# AD620_AC.net
KiCad netlist of a schematic drawn in EAGLE
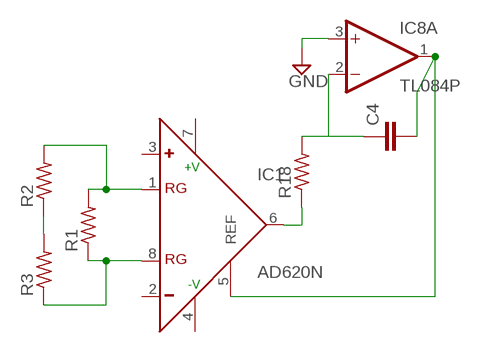
[diagram p0: schematic, sheet 1]

(export (version "E")
  (design (tool "Eeschema 10.0.6"))
  (components
    (comp (ref "C4")
      (value "C-EU050-030X075")
      (footprint "eagle-import:C050-030X075")
      (libsource (lib "eagle-import") (part "C-EU050-030X075"))
    )
    (comp (ref "IC1")
      (value "AD620N")
      (footprint "eagle-import:DIL08")
      (fields (field (name "MF") "ALTERA CORPORATION") (field (name "MPN") "AD620AN"))
      (libsource (lib "eagle-import") (part "AD620N"))
    )
    (comp (ref "IC8")
      (value "TL084P")
      (footprint "eagle-import:DIL14")
      (libsource (lib "eagle-import") (part "TL084P"))
    )
    (comp (ref "R1")
      (value "R-US_0204/5")
      (footprint "eagle-import:0204_5")
      (libsource (lib "eagle-import") (part "R-US_0204/5"))
    )
    (comp (ref "R2")
      (value "R-US_0204/5")
      (footprint "eagle-import:0204_5")
      (libsource (lib "eagle-import") (part "R-US_0204/5"))
    )
    (comp (ref "R3")
      (value "R-US_0204/5")
      (footprint "eagle-import:0204_5")
      (libsource (lib "eagle-import") (part "R-US_0204/5"))
    )
    (comp (ref "R18")
      (value "R-US_0204/5")
      (footprint "eagle-import:0204_5")
      (libsource (lib "eagle-import") (part "R-US_0204/5"))
    )
  )
  (nets
    (net (code "1") (name "/+V") (class "Default")
      (node (ref "IC1") (pin "7") (pinfunction "+V_7") (pintype "power_in"))
    )
    (net (code "2") (name "/-V") (class "Default")
      (node (ref "IC1") (pin "4") (pinfunction "-V_4") (pintype "power_in"))
    )
    (net (code "3") (name "GND") (class "Default")
      (node (ref "IC8") (pin "3") (pinfunction "+IN_3") (pintype "input"))
    )
    (net (code "4") (name "Net-(IC1-OUT)") (class "Default")
      (node (ref "IC1") (pin "6") (pinfunction "OUT_6") (pintype "output"))
      (node (ref "R18") (pin "1") (pinfunction "1_1") (pintype "passive"))
    )
    (net (code "5") (name "Net-(IC1-REF)") (class "Default")
      (node (ref "C4") (pin "2") (pinfunction "2_2") (pintype "passive"))
      (node (ref "IC1") (pin "5") (pinfunction "REF_5") (pintype "passive"))
      (node (ref "IC8") (pin "1") (pinfunction "OUT_1") (pintype "output"))
    )
    (net (code "6") (name "Net-(IC1-RG-Pad1)") (class "Default")
      (node (ref "IC1") (pin "1") (pinfunction "RG_1") (pintype "passive"))
      (node (ref "R1") (pin "2") (pinfunction "2_2") (pintype "passive"))
      (node (ref "R2") (pin "2") (pinfunction "2_2") (pintype "passive"))
    )
    (net (code "7") (name "Net-(IC1-RG-Pad8)") (class "Default")
      (node (ref "IC1") (pin "8") (pinfunction "RG_8") (pintype "passive"))
      (node (ref "R1") (pin "1") (pinfunction "1_1") (pintype "passive"))
      (node (ref "R3") (pin "1") (pinfunction "1_1") (pintype "passive"))
    )
    (net (code "8") (name "Net-(IC8A--IN)") (class "Default")
      (node (ref "C4") (pin "1") (pinfunction "1_1") (pintype "passive"))
      (node (ref "IC8") (pin "2") (pinfunction "-IN_2") (pintype "input"))
      (node (ref "R18") (pin "2") (pinfunction "2_2") (pintype "passive"))
    )
    (net (code "9") (name "Net-(R2-Pad1)") (class "Default")
      (node (ref "R2") (pin "1") (pinfunction "1_1") (pintype "passive"))
      (node (ref "R3") (pin "2") (pinfunction "2_2") (pintype "passive"))
    )
    (net (code "10") (name "unconnected-(IC1-+-Pad3)") (class "Default")
      (node (ref "IC1") (pin "3") (pinfunction "+_3") (pintype "input"))
    )
    (net (code "11") (name "unconnected-(IC1---Pad2)") (class "Default")
      (node (ref "IC1") (pin "2") (pinfunction "-_2") (pintype "input"))
    )
  )
)
